# fillcap_lp.net
KiCad netlist of a schematic drawn in Altium Designer
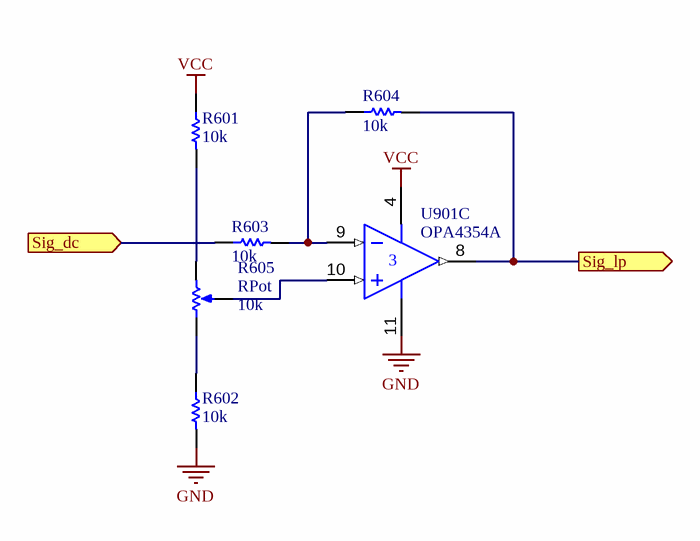
[diagram p0: fillcap_lp.SchDoc]

(export (version "E")
  (design (tool "Eeschema 10.0.6"))
  (components
    (comp (ref "R601")
      (value "10k")
      (footprint "ERA-0805")
      (fields (field (name "PUBLISHER") "Altium Limited"))
      (libsource (lib "Panasonic Resistor") (part "ERAS"))
    )
    (comp (ref "R602")
      (value "10k")
      (footprint "ERA-0805")
      (fields (field (name "PUBLISHER") "Altium Limited"))
      (libsource (lib "Panasonic Resistor") (part "ERAS"))
    )
    (comp (ref "R603")
      (value "10k")
      (footprint "ERA-0805")
      (fields (field (name "PUBLISHER") "Altium Limited"))
      (libsource (lib "Panasonic Resistor") (part "ERAS"))
    )
    (comp (ref "R604")
      (value "10k")
      (footprint "ERA-0805")
      (fields (field (name "PUBLISHER") "Altium Limited"))
      (libsource (lib "Panasonic Resistor") (part "ERAS"))
    )
    (comp (ref "R605")
      (value "RPot")
      (footprint "VR5")
      (description "Potentiometer")
      (fields (field (name "ALTIUM_VALUE") "10k") (field (name "PUBLISHER") "Altium Limited"))
      (libsource (lib "Miscellaneous Devices") (part "RPot"))
    )
    (comp (ref "U901")
      (value "OPA4354A")
      (footprint "D014_N")
      (description "Quadruple Operational Amplifier")
      (fields (field (name "PUBLISHER") "Altium Limited"))
      (libsource (lib "TI Operational Amplifier") (part "LM324AD"))
    )
  )
  (nets
    (net (code "1") (name "/Sig_dc") (class "Default")
      (node (ref "R603") (pin "1") (pinfunction "1_1") (pintype "passive"))
    )
    (net (code "2") (name "/Sig_lp") (class "Default")
      (node (ref "R604") (pin "2") (pinfunction "2_2") (pintype "passive"))
      (node (ref "U901") (pin "8") (pinfunction "OUT_8") (pintype "output"))
    )
    (net (code "3") (name "GND") (class "Default")
      (node (ref "R602") (pin "2") (pinfunction "2_2") (pintype "passive"))
      (node (ref "U901") (pin "11") (pinfunction "V-_11") (pintype "power_in"))
    )
    (net (code "4") (name "Net-(R605-BOT)") (class "Default")
      (node (ref "R601") (pin "2") (pinfunction "2_2") (pintype "passive"))
      (node (ref "R605") (pin "2") (pinfunction "BOT_2") (pintype "passive"))
    )
    (net (code "5") (name "Net-(R605-TAP)") (class "Default")
      (node (ref "R605") (pin "3") (pinfunction "TAP_3") (pintype "passive"))
      (node (ref "U901") (pin "10") (pinfunction "IN+_10") (pintype "input"))
    )
    (net (code "6") (name "Net-(R605-TOP)") (class "Default")
      (node (ref "R602") (pin "1") (pinfunction "1_1") (pintype "passive"))
      (node (ref "R605") (pin "1") (pinfunction "TOP_1") (pintype "passive"))
    )
    (net (code "7") (name "Net-(U901C-IN-)") (class "Default")
      (node (ref "R603") (pin "2") (pinfunction "2_2") (pintype "passive"))
      (node (ref "R604") (pin "1") (pinfunction "1_1") (pintype "passive"))
      (node (ref "U901") (pin "9") (pinfunction "IN-_9") (pintype "input"))
    )
    (net (code "8") (name "VCC") (class "Default")
      (node (ref "R601") (pin "1") (pinfunction "1_1") (pintype "passive"))
      (node (ref "U901") (pin "4") (pinfunction "V+_4") (pintype "power_in"))
    )
  )
)
